# ldr.net
KiCad netlist of a schematic drawn in EAGLE
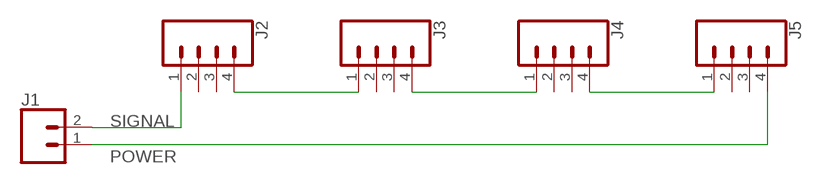
[diagram p0: schematic, sheet 1]

(export (version "E")
  (design (tool "Eeschema 10.0.6"))
  (components
    (comp (ref "J1")
      (value "CONN_02")
      (footprint "eagle-import:1X02")
      (libsource (lib "eagle-import") (part "CONN_02"))
    )
    (comp (ref "J2")
      (value "CONN_04")
      (footprint "eagle-import:1X04")
      (libsource (lib "eagle-import") (part "CONN_04"))
    )
    (comp (ref "J3")
      (value "CONN_04")
      (footprint "eagle-import:1X04")
      (libsource (lib "eagle-import") (part "CONN_04"))
    )
    (comp (ref "J4")
      (value "CONN_04")
      (footprint "eagle-import:1X04")
      (libsource (lib "eagle-import") (part "CONN_04"))
    )
    (comp (ref "J5")
      (value "CONN_04")
      (footprint "eagle-import:1X04")
      (libsource (lib "eagle-import") (part "CONN_04"))
    )
  )
  (nets
    (net (code "1") (name "/POWER") (class "Default")
      (node (ref "J1") (pin "1") (pinfunction "1_1") (pintype "passive"))
      (node (ref "J5") (pin "4") (pinfunction "4_4") (pintype "passive"))
    )
    (net (code "2") (name "/SIGNAL") (class "Default")
      (node (ref "J1") (pin "2") (pinfunction "2_2") (pintype "passive"))
      (node (ref "J2") (pin "1") (pinfunction "1_1") (pintype "passive"))
    )
    (net (code "3") (name "Net-(J2-Pad4)") (class "Default")
      (node (ref "J2") (pin "4") (pinfunction "4_4") (pintype "passive"))
      (node (ref "J3") (pin "1") (pinfunction "1_1") (pintype "passive"))
    )
    (net (code "4") (name "Net-(J3-Pad4)") (class "Default")
      (node (ref "J3") (pin "4") (pinfunction "4_4") (pintype "passive"))
      (node (ref "J4") (pin "1") (pinfunction "1_1") (pintype "passive"))
    )
    (net (code "5") (name "Net-(J4-Pad4)") (class "Default")
      (node (ref "J4") (pin "4") (pinfunction "4_4") (pintype "passive"))
      (node (ref "J5") (pin "1") (pinfunction "1_1") (pintype "passive"))
    )
    (net (code "6") (name "unconnected-(J2-Pad2)") (class "Default")
      (node (ref "J2") (pin "2") (pinfunction "2_2") (pintype "passive"))
    )
    (net (code "7") (name "unconnected-(J2-Pad3)") (class "Default")
      (node (ref "J2") (pin "3") (pinfunction "3_3") (pintype "passive"))
    )
    (net (code "8") (name "unconnected-(J3-Pad2)") (class "Default")
      (node (ref "J3") (pin "2") (pinfunction "2_2") (pintype "passive"))
    )
    (net (code "9") (name "unconnected-(J3-Pad3)") (class "Default")
      (node (ref "J3") (pin "3") (pinfunction "3_3") (pintype "passive"))
    )
    (net (code "10") (name "unconnected-(J4-Pad2)") (class "Default")
      (node (ref "J4") (pin "2") (pinfunction "2_2") (pintype "passive"))
    )
    (net (code "11") (name "unconnected-(J4-Pad3)") (class "Default")
      (node (ref "J4") (pin "3") (pinfunction "3_3") (pintype "passive"))
    )
    (net (code "12") (name "unconnected-(J5-Pad2)") (class "Default")
      (node (ref "J5") (pin "2") (pinfunction "2_2") (pintype "passive"))
    )
    (net (code "13") (name "unconnected-(J5-Pad3)") (class "Default")
      (node (ref "J5") (pin "3") (pinfunction "3_3") (pintype "passive"))
    )
  )
)
